# Shift_Register.net
KiCad netlist of a schematic drawn in Altium Designer
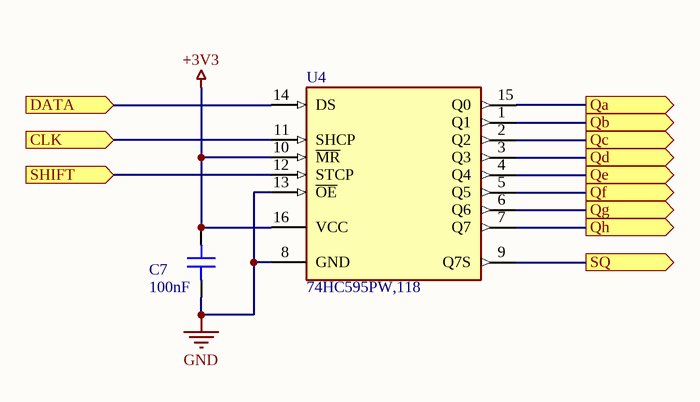
[diagram p0: Shift_Register.SchDoc]

(export (version "E")
  (design (tool "Eeschema 10.0.6"))
  (components
    (comp (ref "C7")
      (value "CL10B104KO8NNNC")
      (footprint "CAPC1608X08N")
      (fields
        (field (name "VOLTAGE") "16V")
        (field (name "MANUFACTURER") "SAMSUNG ELECTRO-MECHANICS")
        (field (name "CAPACITANCE") "100nF")
        (field (name "TOLERANCE") "10%")
      )
      (libsource (lib "Circuit Craft LAB") (part "Capacitor"))
    )
    (comp (ref "U4")
      (value "74HC595PW,118")
      (footprint "SOP65P640X110-16N")
      (description "74HC Series 6 V 3-St 8-Bit Serial-In Serial/Parallel-Out Shift Register-TSSOP-16")
      (fields (field (name "MANUFACTURER") "NXP"))
      (libsource (lib "Circuit Craft LAB") (part "74HC595PW,118"))
    )
  )
  (nets
    (net (code "1") (name "+3V3") (class "Default")
      (node (ref "C7") (pin "2") (pinfunction "2_2") (pintype "passive"))
      (node (ref "U4") (pin "10") (pinfunction "~{MR}_10") (pintype "input"))
      (node (ref "U4") (pin "16") (pinfunction "VCC_16") (pintype "power_in"))
    )
    (net (code "2") (name "/CLK") (class "Default")
      (node (ref "U4") (pin "11") (pinfunction "SHCP_11") (pintype "input"))
    )
    (net (code "3") (name "/DATA") (class "Default")
      (node (ref "U4") (pin "14") (pinfunction "DS_14") (pintype "input"))
    )
    (net (code "4") (name "/Qa") (class "Default")
      (node (ref "U4") (pin "15") (pinfunction "Q0_15") (pintype "output"))
    )
    (net (code "5") (name "/Qb") (class "Default")
      (node (ref "U4") (pin "1") (pinfunction "Q1_1") (pintype "output"))
    )
    (net (code "6") (name "/Qc") (class "Default")
      (node (ref "U4") (pin "2") (pinfunction "Q2_2") (pintype "output"))
    )
    (net (code "7") (name "/Qd") (class "Default")
      (node (ref "U4") (pin "3") (pinfunction "Q3_3") (pintype "output"))
    )
    (net (code "8") (name "/Qe") (class "Default")
      (node (ref "U4") (pin "4") (pinfunction "Q4_4") (pintype "output"))
    )
    (net (code "9") (name "/Qf") (class "Default")
      (node (ref "U4") (pin "5") (pinfunction "Q5_5") (pintype "output"))
    )
    (net (code "10") (name "/Qg") (class "Default")
      (node (ref "U4") (pin "6") (pinfunction "Q6_6") (pintype "output"))
    )
    (net (code "11") (name "/Qh") (class "Default")
      (node (ref "U4") (pin "7") (pinfunction "Q7_7") (pintype "output"))
    )
    (net (code "12") (name "/SHIFT") (class "Default")
      (node (ref "U4") (pin "12") (pinfunction "STCP_12") (pintype "input"))
    )
    (net (code "13") (name "/SQ") (class "Default")
      (node (ref "U4") (pin "9") (pinfunction "Q7S_9") (pintype "output"))
    )
    (net (code "14") (name "GND") (class "Default")
      (node (ref "C7") (pin "1") (pinfunction "1_1") (pintype "passive"))
      (node (ref "U4") (pin "13") (pinfunction "~{OE}_13") (pintype "input"))
      (node (ref "U4") (pin "8") (pinfunction "GND_8") (pintype "power_in"))
    )
  )
)
